# sparkfun-samd21g-r3.net
KiCad netlist of a schematic drawn in EAGLE
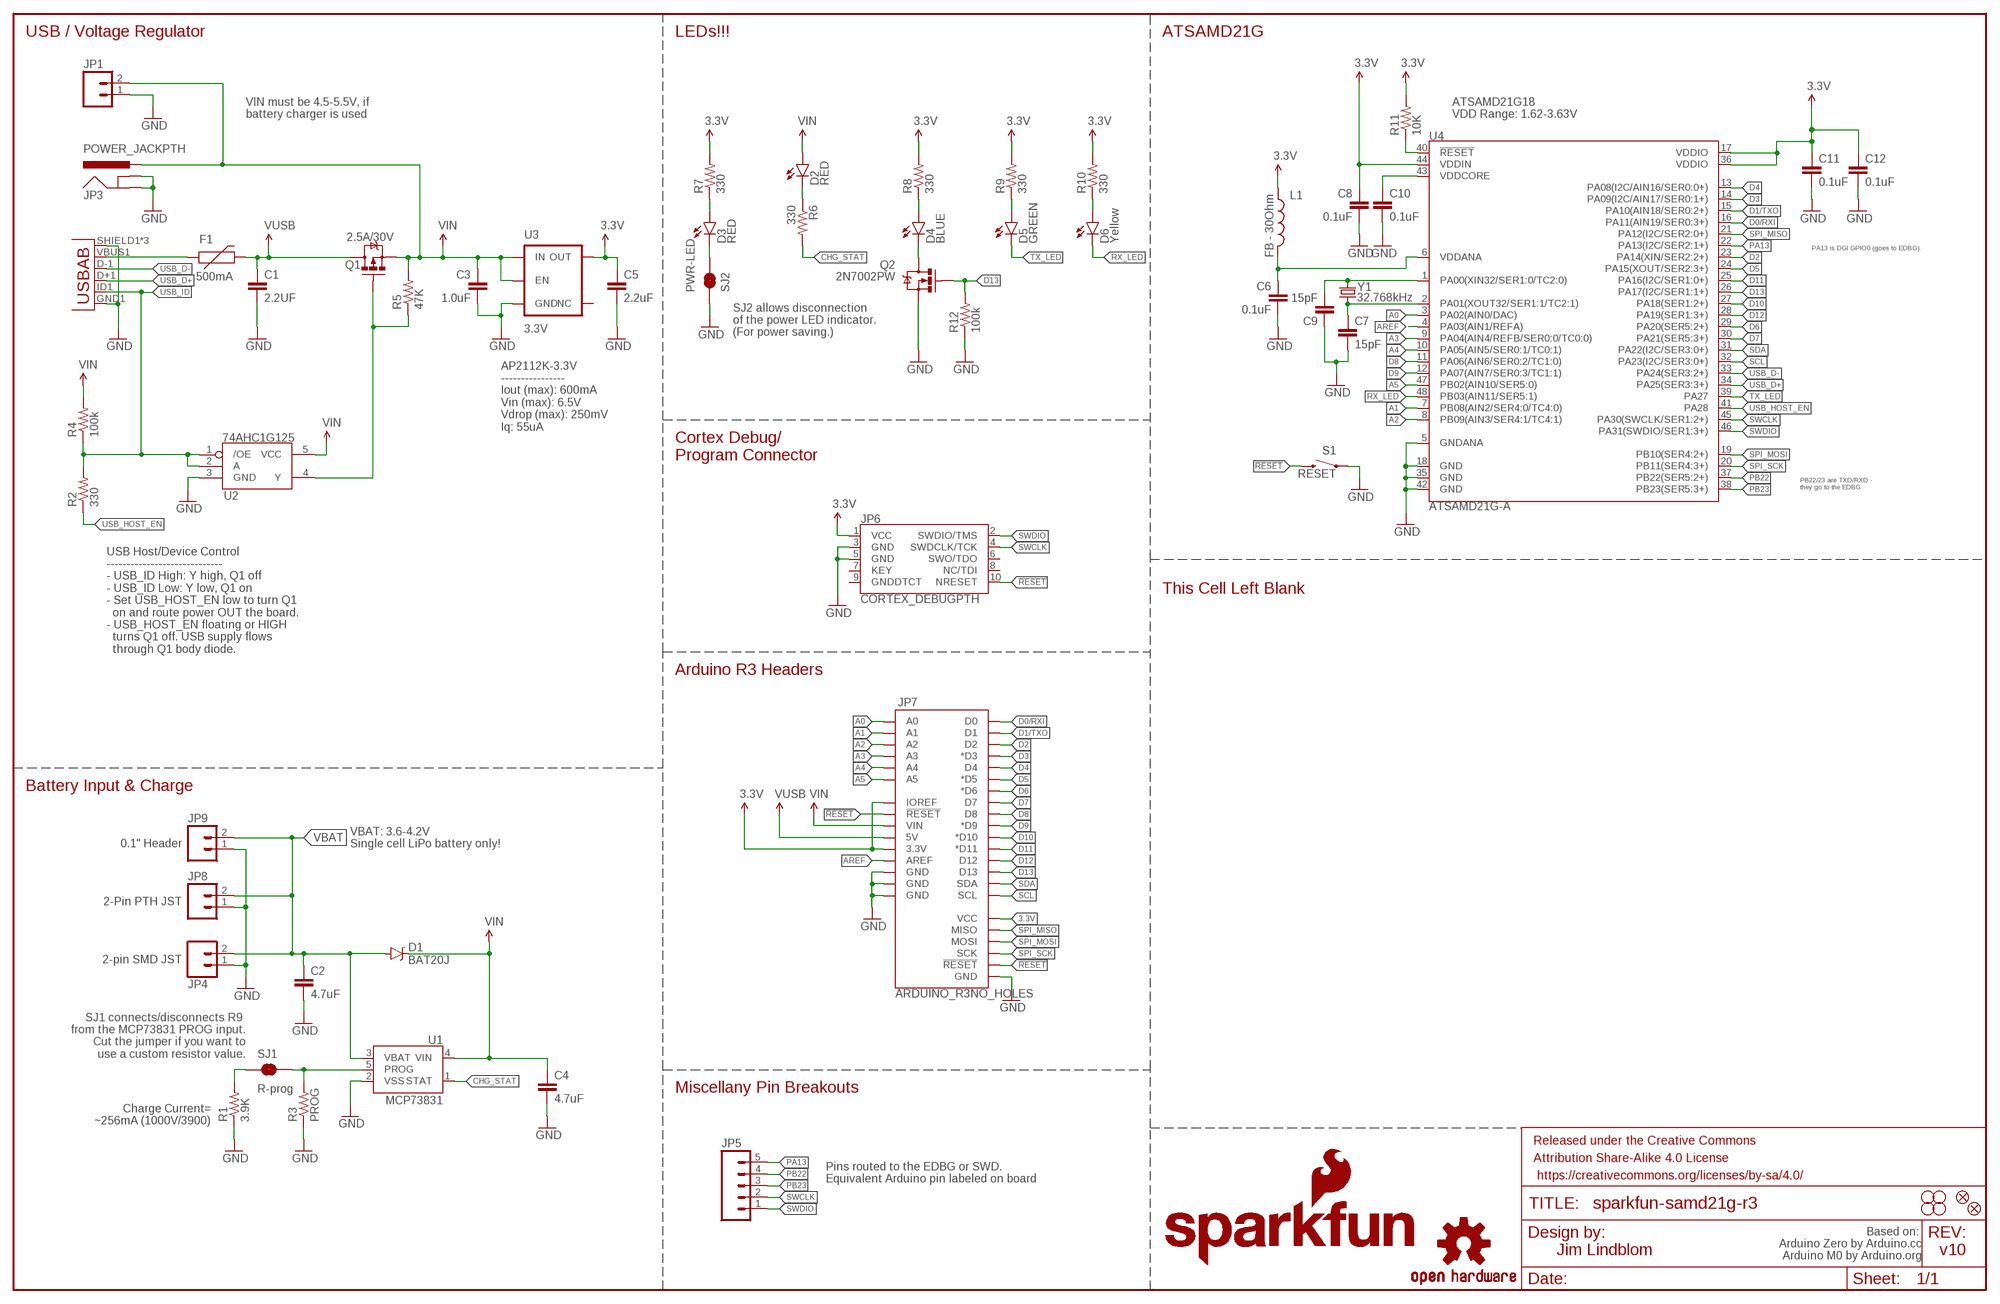
[diagram p0: schematic, sheet 1]

(export (version "E")
  (design (tool "Eeschema 10.0.6"))
  (components
    (comp (ref "C1")
      (value "2.2UF")
      (footprint "eagle-import:1206")
      (libsource (lib "eagle-import") (part "2.2UF50V10%(1206)"))
    )
    (comp (ref "C2")
      (value "4.7uF")
      (footprint "eagle-import:0603-CAP")
      (libsource (lib "eagle-import") (part "4.7UF-6.3V-10%(0603)0603"))
    )
    (comp (ref "C3")
      (value "1.0uF")
      (footprint "eagle-import:0805-CAP")
      (libsource (lib "eagle-import") (part "1.0UF-25V-+80/-20(0805){dblquote}"))
    )
    (comp (ref "C4")
      (value "4.7uF")
      (footprint "eagle-import:0603-CAP")
      (libsource (lib "eagle-import") (part "4.7UF-6.3V-10%(0603)0603"))
    )
    (comp (ref "C5")
      (value "2.2uF")
      (footprint "eagle-import:0603-CAP")
      (libsource (lib "eagle-import") (part "2.2UF-10V-20%(0603)"))
    )
    (comp (ref "C6")
      (value "0.1uF")
      (footprint "eagle-import:0603-CAP")
      (libsource (lib "eagle-import") (part "0.1UF-25V(+80/-20%)(0603)"))
    )
    (comp (ref "C7")
      (value "15pF")
      (footprint "eagle-import:0603-CAP")
      (libsource (lib "eagle-import") (part "15PF-50V-5%(0603)"))
    )
    (comp (ref "C8")
      (value "0.1uF")
      (footprint "eagle-import:0603-CAP")
      (libsource (lib "eagle-import") (part "0.1UF-25V(+80/-20%)(0603)"))
    )
    (comp (ref "C9")
      (value "15pF")
      (footprint "eagle-import:0603-CAP")
      (libsource (lib "eagle-import") (part "15PF-50V-5%(0603)"))
    )
    (comp (ref "C10")
      (value "0.1uF")
      (footprint "eagle-import:0603-CAP")
      (libsource (lib "eagle-import") (part "0.1UF-25V(+80/-20%)(0603)"))
    )
    (comp (ref "C11")
      (value "0.1uF")
      (footprint "eagle-import:0603-CAP")
      (libsource (lib "eagle-import") (part "0.1UF-25V(+80/-20%)(0603)"))
    )
    (comp (ref "C12")
      (value "0.1uF")
      (footprint "eagle-import:0603-CAP")
      (libsource (lib "eagle-import") (part "0.1UF-25V(+80/-20%)(0603)"))
    )
    (comp (ref "D1")
      (value "BAT20J")
      (footprint "eagle-import:SOD-323")
      (libsource (lib "eagle-import") (part "DIODE-SCHOTTKY-BAT20J"))
    )
    (comp (ref "D2")
      (value "RED")
      (footprint "eagle-import:LED-0603")
      (libsource (lib "eagle-import") (part "LED-RED0603"))
    )
    (comp (ref "D3")
      (value "RED")
      (footprint "eagle-import:LED-0603")
      (libsource (lib "eagle-import") (part "LED-RED0603"))
    )
    (comp (ref "D4")
      (value "BLUE")
      (footprint "eagle-import:LED-0603")
      (libsource (lib "eagle-import") (part "LED-BLUE0603"))
    )
    (comp (ref "D5")
      (value "GREEN")
      (footprint "eagle-import:LED-0603")
      (libsource (lib "eagle-import") (part "LED-GREEN0603"))
    )
    (comp (ref "D6")
      (value "Yellow")
      (footprint "eagle-import:LED-0603")
      (libsource (lib "eagle-import") (part "LED-YELLOW0603"))
    )
    (comp (ref "F1")
      (value "500mA")
      (footprint "eagle-import:PTC-1206")
      (libsource (lib "eagle-import") (part "PTCSMD"))
    )
    (comp (ref "FID1")
      (value "FIDUCIAL1X2")
      (footprint "eagle-import:FIDUCIAL-1X2")
      (libsource (lib "eagle-import") (part "FIDUCIAL1X2"))
    )
    (comp (ref "FID2")
      (value "FIDUCIAL1X2")
      (footprint "eagle-import:FIDUCIAL-1X2")
      (libsource (lib "eagle-import") (part "FIDUCIAL1X2"))
    )
    (comp (ref "FRAME1")
      (value "FRAME-LEDGER")
      (footprint "eagle-import:CREATIVE_COMMONS")
      (libsource (lib "eagle-import") (part "FRAME-LEDGER"))
    )
    (comp (ref "JP1")
      (value "M02PTH")
      (footprint "eagle-import:1X02")
      (libsource (lib "eagle-import") (part "M02PTH"))
    )
    (comp (ref "JP2")
      (value "USB-ABCONN-11794")
      (footprint "eagle-import:USB-AB-MICRO-SMD_V03")
      (libsource (lib "eagle-import") (part "USB-ABCONN-11794"))
    )
    (comp (ref "JP3")
      (value "POWER_JACKPTH")
      (footprint "eagle-import:POWER_JACK_PTH")
      (libsource (lib "eagle-import") (part "POWER_JACKPTH"))
    )
    (comp (ref "JP4")
      (value "M02-JST-2MM-SMT")
      (footprint "eagle-import:JST-2-SMD")
      (libsource (lib "eagle-import") (part "M02-JST-2MM-SMT"))
    )
    (comp (ref "JP5")
      (value "M05NO_SILK")
      (footprint "eagle-import:1X05_NO_SILK")
      (libsource (lib "eagle-import") (part "M05NO_SILK"))
    )
    (comp (ref "JP6")
      (value "CORTEX_DEBUGPTH")
      (footprint "eagle-import:2X5-PTH-1.27MM")
      (libsource (lib "eagle-import") (part "CORTEX_DEBUGPTH"))
    )
    (comp (ref "JP7")
      (value "ARDUINO_R3NO_HOLES")
      (footprint "eagle-import:ARDUINO_R3_NO_HOLES")
      (libsource (lib "eagle-import") (part "ARDUINO_R3NO_HOLES"))
    )
    (comp (ref "JP8")
      (value "M02-JST-2-PTH-NO_SILK")
      (footprint "eagle-import:JST-2-PTH-NS")
      (libsource (lib "eagle-import") (part "M02-JST-2-PTH-NO_SILK"))
    )
    (comp (ref "JP9")
      (value "M021X02_NO_SILK")
      (footprint "eagle-import:1X02_NO_SILK")
      (libsource (lib "eagle-import") (part "M021X02_NO_SILK"))
    )
    (comp (ref "L1")
      (value "FB - 30Ohm")
      (footprint "eagle-import:0603")
      (libsource (lib "eagle-import") (part "INDUCTOR0603"))
    )
    (comp (ref "LOGO1")
      (value "SFE_LOGO_NAME_FLAME.2_INCH")
      (footprint "eagle-import:SFE_LOGO_NAME_FLAME_.2")
      (libsource (lib "eagle-import") (part "SFE_LOGO_NAME_FLAME.2_INCH"))
    )
    (comp (ref "LOGO2")
      (value "SFE_LOGO_NAME_FLAME.4_INCH")
      (footprint "eagle-import:SFE_LOGO_NAME_FLAME_.4")
      (libsource (lib "eagle-import") (part "SFE_LOGO_NAME_FLAME.4_INCH"))
    )
    (comp (ref "LOGO3")
      (value "OSHW-LOGOS")
      (footprint "eagle-import:OSHW-LOGO-S")
      (libsource (lib "eagle-import") (part "OSHW-LOGOS"))
    )
    (comp (ref "LOGO4")
      (value "OSHW-LOGOL")
      (footprint "eagle-import:OSHW-LOGO-L")
      (libsource (lib "eagle-import") (part "OSHW-LOGOL"))
    )
    (comp (ref "Q1")
      (value "2.5A/30V")
      (footprint "eagle-import:SOT23-3")
      (libsource (lib "eagle-import") (part "MOSFET-PCHANNELDMG2307L"))
    )
    (comp (ref "Q2")
      (value "2N7002PW")
      (footprint "eagle-import:SOT323")
      (libsource (lib "eagle-import") (part "MOSFET-NCHANNEL2N7002PW"))
    )
    (comp (ref "R1")
      (value "3.9K")
      (footprint "eagle-import:0603")
      (libsource (lib "eagle-import") (part "3.9KOHM1/10W1%(0603)"))
    )
    (comp (ref "R2")
      (value "330")
      (footprint "eagle-import:0603-RES")
      (libsource (lib "eagle-import") (part "330OHM1/10W1%(0603)"))
    )
    (comp (ref "R3")
      (value "PROG")
      (footprint "eagle-import:1_6W-RES")
      (libsource (lib "eagle-import") (part "RESISTORPTH-1/6W"))
    )
    (comp (ref "R4")
      (value "100k")
      (footprint "eagle-import:0603-RES")
      (libsource (lib "eagle-import") (part "100KOHM-1/10W-1%(0603)"))
    )
    (comp (ref "R5")
      (value "47K")
      (footprint "eagle-import:0603-RES")
      (libsource (lib "eagle-import") (part "47KOHM1/10W1%(0603)"))
    )
    (comp (ref "R6")
      (value "330")
      (footprint "eagle-import:0603-RES")
      (libsource (lib "eagle-import") (part "330OHM1/10W1%(0603)"))
    )
    (comp (ref "R7")
      (value "330")
      (footprint "eagle-import:0603-RES")
      (libsource (lib "eagle-import") (part "330OHM1/10W1%(0603)"))
    )
    (comp (ref "R8")
      (value "330")
      (footprint "eagle-import:0603-RES")
      (libsource (lib "eagle-import") (part "330OHM1/10W1%(0603)"))
    )
    (comp (ref "R9")
      (value "330")
      (footprint "eagle-import:0603-RES")
      (libsource (lib "eagle-import") (part "330OHM1/10W1%(0603)"))
    )
    (comp (ref "R10")
      (value "330")
      (footprint "eagle-import:0603-RES")
      (libsource (lib "eagle-import") (part "330OHM1/10W1%(0603)"))
    )
    (comp (ref "R11")
      (value "10K")
      (footprint "eagle-import:0603-RES")
      (libsource (lib "eagle-import") (part "10KOHM-1/10W-1%(0603)0603"))
    )
    (comp (ref "R12")
      (value "100k")
      (footprint "eagle-import:0603-RES")
      (libsource (lib "eagle-import") (part "100KOHM-1/10W-1%(0603)"))
    )
    (comp (ref "S1")
      (value "RESET")
      (footprint "eagle-import:TACTILE-SWITCH-SMD")
      (libsource (lib "eagle-import") (part "SWITCH-MOMENTARY-2SMD"))
    )
    (comp (ref "SJ1")
      (value "R-prog")
      (footprint "eagle-import:PAD-JUMPER-2-NC_BY_TRACE_YES_SILK")
      (libsource (lib "eagle-import") (part "JUMPER-PAD-2-NC_BY_TRACE"))
    )
    (comp (ref "SJ2")
      (value "PWR-LED")
      (footprint "eagle-import:PAD-JUMPER-2-NC_BY_TRACE_NO_SILK")
      (libsource (lib "eagle-import") (part "JUMPER-PAD-2-NC_BY_TRACENO_SILK"))
    )
    (comp (ref "STANDOFF1")
      (value "STAND-OFF")
      (footprint "eagle-import:STAND-OFF")
      (libsource (lib "eagle-import") (part "STAND-OFF"))
    )
    (comp (ref "STANDOFF2")
      (value "STAND-OFF")
      (footprint "eagle-import:STAND-OFF")
      (libsource (lib "eagle-import") (part "STAND-OFF"))
    )
    (comp (ref "STANDOFF3")
      (value "STAND-OFF")
      (footprint "eagle-import:STAND-OFF")
      (libsource (lib "eagle-import") (part "STAND-OFF"))
    )
    (comp (ref "STANDOFF4")
      (value "STAND-OFF")
      (footprint "eagle-import:STAND-OFF")
      (libsource (lib "eagle-import") (part "STAND-OFF"))
    )
    (comp (ref "U1")
      (value "MCP73831")
      (footprint "eagle-import:SOT23-5")
      (libsource (lib "eagle-import") (part "MCP73831"))
    )
    (comp (ref "U2")
      (value "74AHC1G125")
      (footprint "eagle-import:SOT23-5")
      (libsource (lib "eagle-import") (part "74AHC1G125"))
    )
    (comp (ref "U3")
      (value "3.3V")
      (footprint "eagle-import:SOT23-5")
      (libsource (lib "eagle-import") (part "V_REG_AP2112K-3.3V"))
    )
    (comp (ref "U4")
      (value "ATSAMD21G-A")
      (footprint "eagle-import:TQFP-48")
      (libsource (lib "eagle-import") (part "ATSAMD21G-A"))
    )
    (comp (ref "Y1")
      (value "32.768kHz")
      (footprint "eagle-import:CRYSTAL-SMD-3.2X1.5MM")
      (libsource (lib "eagle-import") (part "CRYSTAL3.2X1.5MM"))
    )
  )
  (nets
    (net (code "1") (name "/~{RESET}") (class "Default")
      (node (ref "JP6") (pin "10") (pinfunction "NRESET_10") (pintype "bidirectional"))
      (node (ref "JP7") (pin "RESET@1") (pinfunction "~{RESET}_RESET@1") (pintype "bidirectional"))
      (node (ref "JP7") (pin "RESET@2") (pinfunction "~{RESET}_RESET@2") (pintype "bidirectional"))
      (node (ref "R11") (pin "1") (pinfunction "1_1") (pintype "passive"))
      (node (ref "S1") (pin "3") (pinfunction "2_3") (pintype "passive"))
      (node (ref "U4") (pin "40") (pinfunction "~{RESET}_40") (pintype "bidirectional"))
    )
    (net (code "2") (name "3.3V") (class "Default")
      (node (ref "C11") (pin "1") (pinfunction "1_1") (pintype "passive"))
      (node (ref "C12") (pin "1") (pinfunction "1_1") (pintype "passive"))
      (node (ref "C5") (pin "1") (pinfunction "1_1") (pintype "passive"))
      (node (ref "C8") (pin "1") (pinfunction "1_1") (pintype "passive"))
      (node (ref "JP6") (pin "1") (pinfunction "VCC_1") (pintype "bidirectional"))
      (node (ref "JP7") (pin "3.3V") (pinfunction "3.3V_3.3V") (pintype "bidirectional"))
      (node (ref "JP7") (pin "IOREF") (pinfunction "IOREF_IOREF") (pintype "bidirectional"))
      (node (ref "JP7") (pin "VCC") (pinfunction "VCC_VCC") (pintype "bidirectional"))
      (node (ref "L1") (pin "1") (pinfunction "1_1") (pintype "passive"))
      (node (ref "R10") (pin "2") (pinfunction "2_2") (pintype "passive"))
      (node (ref "R11") (pin "2") (pinfunction "2_2") (pintype "passive"))
      (node (ref "R7") (pin "2") (pinfunction "2_2") (pintype "passive"))
      (node (ref "R8") (pin "2") (pinfunction "2_2") (pintype "passive"))
      (node (ref "R9") (pin "2") (pinfunction "2_2") (pintype "passive"))
      (node (ref "U3") (pin "5") (pinfunction "OUT_5") (pintype "passive"))
      (node (ref "U4") (pin "17") (pinfunction "VDDIO_17") (pintype "bidirectional"))
      (node (ref "U4") (pin "36") (pinfunction "VDDIO_36") (pintype "bidirectional"))
      (node (ref "U4") (pin "44") (pinfunction "VDDIN_44") (pintype "bidirectional"))
    )
    (net (code "3") (name "A0") (class "Default")
      (node (ref "JP7") (pin "A0") (pinfunction "A0_A0") (pintype "bidirectional"))
      (node (ref "U4") (pin "3") (pinfunction "PA02(AIN0/DAC)_3") (pintype "bidirectional"))
    )
    (net (code "4") (name "A1") (class "Default")
      (node (ref "JP7") (pin "A1") (pinfunction "A1_A1") (pintype "bidirectional"))
      (node (ref "U4") (pin "7") (pinfunction "PB08(AIN2/SER4:0/TC4:0)_7") (pintype "bidirectional"))
    )
    (net (code "5") (name "A2") (class "Default")
      (node (ref "JP7") (pin "A2") (pinfunction "A2_A2") (pintype "bidirectional"))
      (node (ref "U4") (pin "8") (pinfunction "PB09(AIN3/SER4:1/TC4:1)_8") (pintype "bidirectional"))
    )
    (net (code "6") (name "A3") (class "Default")
      (node (ref "JP7") (pin "A3") (pinfunction "A3_A3") (pintype "bidirectional"))
      (node (ref "U4") (pin "9") (pinfunction "PA04(AIN4/REFB/SER0:0/TC0:0)_9") (pintype "bidirectional"))
    )
    (net (code "7") (name "A4") (class "Default")
      (node (ref "JP7") (pin "A4") (pinfunction "A4_A4") (pintype "bidirectional"))
      (node (ref "U4") (pin "10") (pinfunction "PA05(AIN5/SER0:1/TC0:1)_10") (pintype "bidirectional"))
    )
    (net (code "8") (name "A5") (class "Default")
      (node (ref "JP7") (pin "A5") (pinfunction "A5_A5") (pintype "bidirectional"))
      (node (ref "U4") (pin "47") (pinfunction "PB02(AIN10/SER5:0)_47") (pintype "bidirectional"))
    )
    (net (code "9") (name "AREF") (class "Default")
      (node (ref "JP7") (pin "AREF") (pinfunction "AREF_AREF") (pintype "bidirectional"))
      (node (ref "U4") (pin "4") (pinfunction "PA03(AIN1/REFA)_4") (pintype "bidirectional"))
    )
    (net (code "10") (name "CHG_STAT") (class "Default")
      (node (ref "R6") (pin "2") (pinfunction "2_2") (pintype "passive"))
      (node (ref "U1") (pin "1") (pinfunction "STAT_1") (pintype "output"))
    )
    (net (code "11") (name "D0{slash}RXI") (class "Default")
      (node (ref "JP7") (pin "D0") (pinfunction "D0_D0") (pintype "bidirectional"))
      (node (ref "U4") (pin "16") (pinfunction "PA11(AIN19/SER0:3+)_16") (pintype "bidirectional"))
    )
    (net (code "12") (name "D1{slash}TXO") (class "Default")
      (node (ref "JP7") (pin "D1") (pinfunction "D1_D1") (pintype "bidirectional"))
      (node (ref "U4") (pin "15") (pinfunction "PA10(AIN18/SER0:2+)_15") (pintype "bidirectional"))
    )
    (net (code "13") (name "D2") (class "Default")
      (node (ref "JP7") (pin "D2") (pinfunction "D2_D2") (pintype "bidirectional"))
      (node (ref "U4") (pin "23") (pinfunction "PA14(XIN/SER2:2+)_23") (pintype "bidirectional"))
    )
    (net (code "14") (name "D3") (class "Default")
      (node (ref "JP7") (pin "D3") (pinfunction "*D3_D3") (pintype "bidirectional"))
      (node (ref "U4") (pin "14") (pinfunction "PA09(I2C/AIN17/SER0:1+)_14") (pintype "bidirectional"))
    )
    (net (code "15") (name "D4") (class "Default")
      (node (ref "JP7") (pin "D4") (pinfunction "D4_D4") (pintype "bidirectional"))
      (node (ref "U4") (pin "13") (pinfunction "PA08(I2C/AIN16/SER0:0+)_13") (pintype "bidirectional"))
    )
    (net (code "16") (name "D5") (class "Default")
      (node (ref "JP7") (pin "D5") (pinfunction "*D5_D5") (pintype "bidirectional"))
      (node (ref "U4") (pin "24") (pinfunction "PA15(XOUT/SER2:3+)_24") (pintype "bidirectional"))
    )
    (net (code "17") (name "D6") (class "Default")
      (node (ref "JP7") (pin "D6") (pinfunction "*D6_D6") (pintype "bidirectional"))
      (node (ref "U4") (pin "29") (pinfunction "PA20(SER5:2+)_29") (pintype "bidirectional"))
    )
    (net (code "18") (name "D7") (class "Default")
      (node (ref "JP7") (pin "D7") (pinfunction "D7_D7") (pintype "bidirectional"))
      (node (ref "U4") (pin "30") (pinfunction "PA21(SER5:3+)_30") (pintype "bidirectional"))
    )
    (net (code "19") (name "D8") (class "Default")
      (node (ref "JP7") (pin "D8") (pinfunction "D8_D8") (pintype "bidirectional"))
      (node (ref "U4") (pin "11") (pinfunction "PA06(AIN6/SER0:2/TC1:0)_11") (pintype "bidirectional"))
    )
    (net (code "20") (name "D9") (class "Default")
      (node (ref "JP7") (pin "D9") (pinfunction "*D9_D9") (pintype "bidirectional"))
      (node (ref "U4") (pin "12") (pinfunction "PA07(AIN7/SER0:3/TC1:1)_12") (pintype "bidirectional"))
    )
    (net (code "21") (name "D10") (class "Default")
      (node (ref "JP7") (pin "D10") (pinfunction "*D10_D10") (pintype "bidirectional"))
      (node (ref "U4") (pin "27") (pinfunction "PA18(SER1:2+)_27") (pintype "bidirectional"))
    )
    (net (code "22") (name "D11") (class "Default")
      (node (ref "JP7") (pin "D11") (pinfunction "*D11_D11") (pintype "bidirectional"))
      (node (ref "U4") (pin "25") (pinfunction "PA16(I2C/SER1:0+)_25") (pintype "bidirectional"))
    )
    (net (code "23") (name "D12") (class "Default")
      (node (ref "JP7") (pin "D12") (pinfunction "D12_D12") (pintype "bidirectional"))
      (node (ref "U4") (pin "28") (pinfunction "PA19(SER1:3+)_28") (pintype "bidirectional"))
    )
    (net (code "24") (name "D13") (class "Default")
      (node (ref "JP7") (pin "D13") (pinfunction "D13_D13") (pintype "bidirectional"))
      (node (ref "Q2") (pin "1") (pinfunction "G_1") (pintype "passive"))
      (node (ref "R12") (pin "2") (pinfunction "2_2") (pintype "passive"))
      (node (ref "U4") (pin "26") (pinfunction "PA17(I2C/SER1:1+)_26") (pintype "bidirectional"))
    )
    (net (code "25") (name "GND") (class "Default")
      (node (ref "C1") (pin "2") (pinfunction "2_2") (pintype "passive"))
      (node (ref "C10") (pin "2") (pinfunction "2_2") (pintype "passive"))
      (node (ref "C11") (pin "2") (pinfunction "2_2") (pintype "passive"))
      (node (ref "C12") (pin "2") (pinfunction "2_2") (pintype "passive"))
      (node (ref "C2") (pin "2") (pinfunction "2_2") (pintype "passive"))
      (node (ref "C3") (pin "2") (pinfunction "2_2") (pintype "passive"))
      (node (ref "C4") (pin "2") (pinfunction "2_2") (pintype "passive"))
      (node (ref "C5") (pin "2") (pinfunction "2_2") (pintype "passive"))
      (node (ref "C6") (pin "2") (pinfunction "2_2") (pintype "passive"))
      (node (ref "C7") (pin "2") (pinfunction "2_2") (pintype "passive"))
      (node (ref "C8") (pin "2") (pinfunction "2_2") (pintype "passive"))
      (node (ref "C9") (pin "1") (pinfunction "1_1") (pintype "passive"))
      (node (ref "JP1") (pin "1") (pinfunction "1_1") (pintype "passive"))
      (node (ref "JP2") (pin "GND1") (pinfunction "GND_GND1") (pintype "bidirectional"))
      (node (ref "JP2") (pin "SHIELD1") (pinfunction "SHIELD_SHIELD1") (pintype "bidirectional"))
      (node (ref "JP2") (pin "SHIELD2") (pinfunction "SHIELD_SHIELD2") (pintype "bidirectional"))
      (node (ref "JP2") (pin "SHIELD3") (pinfunction "SHIELD_SHIELD3") (pintype "bidirectional"))
      (node (ref "JP3") (pin "GND") (pinfunction "GND_GND") (pintype "bidirectional"))
      (node (ref "JP3") (pin "GNDBREAK") (pinfunction "GNDBREAK_GNDBREAK") (pintype "bidirectional"))
      (node (ref "JP4") (pin "1") (pinfunction "2_1") (pintype "passive"))
      (node (ref "JP6") (pin "3") (pinfunction "GND_3") (pintype "bidirectional"))
      (node (ref "JP6") (pin "5") (pinfunction "GND_5") (pintype "bidirectional"))
      (node (ref "JP7") (pin "GND@1") (pinfunction "GND_GND@1") (pintype "bidirectional"))
      (node (ref "JP7") (pin "GND@2") (pinfunction "GND_GND@2") (pintype "bidirectional"))
      (node (ref "JP7") (pin "GND@3") (pinfunction "GND_GND@3") (pintype "bidirectional"))
      (node (ref "JP7") (pin "GND@4") (pinfunction "GND_GND@4") (pintype "bidirectional"))
      (node (ref "JP8") (pin "1") (pinfunction "1_1") (pintype "passive"))
      (node (ref "JP9") (pin "1") (pinfunction "1_1") (pintype "passive"))
      (node (ref "Q2") (pin "2") (pinfunction "S_2") (pintype "passive"))
      (node (ref "R1") (pin "1") (pinfunction "1_1") (pintype "passive"))
      (node (ref "R12") (pin "1") (pinfunction "1_1") (pintype "passive"))
      (node (ref "R3") (pin "1") (pinfunction "1_1") (pintype "passive"))
      (node (ref "S1") (pin "1") (pinfunction "1_1") (pintype "passive"))
      (node (ref "SJ2") (pin "1") (pinfunction "1_1") (pintype "passive"))
      (node (ref "U1") (pin "2") (pinfunction "VSS_2") (pintype "power_in"))
      (node (ref "U2") (pin "3") (pinfunction "GND_3") (pintype "bidirectional"))
      (node (ref "U3") (pin "2") (pinfunction "GND_2") (pintype "input"))
      (node (ref "U4") (pin "18") (pinfunction "GND_18") (pintype "bidirectional"))
      (node (ref "U4") (pin "35") (pinfunction "GND_35") (pintype "bidirectional"))
      (node (ref "U4") (pin "42") (pinfunction "GND_42") (pintype "bidirectional"))
      (node (ref "U4") (pin "5") (pinfunction "GNDANA_5") (pintype "bidirectional"))
    )
    (net (code "26") (name "Net-(D2-PadC)") (class "Default")
      (node (ref "D2") (pin "C") (pinfunction "C_C") (pintype "passive"))
      (node (ref "R6") (pin "1") (pinfunction "1_1") (pintype "passive"))
    )
    (net (code "27") (name "Net-(D3-PadA)") (class "Default")
      (node (ref "D3") (pin "A") (pinfunction "A_A") (pintype "passive"))
      (node (ref "R7") (pin "1") (pinfunction "1_1") (pintype "passive"))
    )
    (net (code "28") (name "Net-(D3-PadC)") (class "Default")
      (node (ref "D3") (pin "C") (pinfunction "C_C") (pintype "passive"))
      (node (ref "SJ2") (pin "2") (pinfunction "2_2") (pintype "passive"))
    )
    (net (code "29") (name "Net-(D4-PadA)") (class "Default")
      (node (ref "D4") (pin "A") (pinfunction "A_A") (pintype "passive"))
      (node (ref "R8") (pin "1") (pinfunction "1_1") (pintype "passive"))
    )
    (net (code "30") (name "Net-(D5-PadA)") (class "Default")
      (node (ref "D5") (pin "A") (pinfunction "A_A") (pintype "passive"))
      (node (ref "R9") (pin "1") (pinfunction "1_1") (pintype "passive"))
    )
    (net (code "31") (name "Net-(D6-PadA)") (class "Default")
      (node (ref "D6") (pin "A") (pinfunction "A_A") (pintype "passive"))
      (node (ref "R10") (pin "1") (pinfunction "1_1") (pintype "passive"))
    )
    (net (code "32") (name "Net-(JP2-VBUS)") (class "Default")
      (node (ref "F1") (pin "1") (pinfunction "1_1") (pintype "bidirectional"))
      (node (ref "JP2") (pin "VBUS1") (pinfunction "VBUS_VBUS1") (pintype "bidirectional"))
    )
    (net (code "33") (name "Net-(Q1-G)") (class "Default")
      (node (ref "Q1") (pin "1") (pinfunction "G_1") (pintype "passive"))
      (node (ref "R5") (pin "1") (pinfunction "1_1") (pintype "passive"))
      (node (ref "U2") (pin "4") (pinfunction "Y_4") (pintype "bidirectional"))
    )
    (net (code "34") (name "Net-(Q2-D)") (class "Default")
      (node (ref "D4") (pin "C") (pinfunction "C_C") (pintype "passive"))
      (node (ref "Q2") (pin "3") (pinfunction "D_3") (pintype "passive"))
    )
    (net (code "35") (name "Net-(R1-Pad2)") (class "Default")
      (node (ref "R1") (pin "2") (pinfunction "2_2") (pintype "passive"))
      (node (ref "SJ1") (pin "1") (pinfunction "1_1") (pintype "passive"))
    )
    (net (code "36") (name "Net-(U1-PROG)") (class "Default")
      (node (ref "R3") (pin "2") (pinfunction "2_2") (pintype "passive"))
      (node (ref "SJ1") (pin "2") (pinfunction "2_2") (pintype "passive"))
      (node (ref "U1") (pin "5") (pinfunction "PROG_5") (pintype "input"))
    )
    (net (code "37") (name "Net-(U4-PA00(XIN32{slash}SER1:0{slash}TC2:0))") (class "Default")
      (node (ref "C9") (pin "2") (pinfunction "2_2") (pintype "passive"))
      (node (ref "U4") (pin "1") (pinfunction "PA00(XIN32/SER1:0/TC2:0)_1") (pintype "bidirectional"))
      (node (ref "Y1") (pin "P$2") (pinfunction "2_P$2") (pintype "passive"))
    )
    (net (code "38") (name "Net-(U4-PA01(XOUT32{slash}SER1:1{slash}TC2:1))") (class "Default")
      (node (ref "C7") (pin "1") (pinfunction "1_1") (pintype "passive"))
      (node (ref "U4") (pin "2") (pinfunction "PA01(XOUT32/SER1:1/TC2:1)_2") (pintype "bidirectional"))
      (node (ref "Y1") (pin "P$1") (pinfunction "1_P$1") (pintype "passive"))
    )
    (net (code "39") (name "Net-(U4-VDDANA)") (class "Default")
      (node (ref "C6") (pin "1") (pinfunction "1_1") (pintype "passive"))
      (node (ref "L1") (pin "2") (pinfunction "2_2") (pintype "passive"))
      (node (ref "U4") (pin "6") (pinfunction "VDDANA_6") (pintype "bidirectional"))
    )
    (net (code "40") (name "Net-(U4-VDDCORE)") (class "Default")
      (node (ref "C10") (pin "1") (pinfunction "1_1") (pintype "passive"))
      (node (ref "U4") (pin "43") (pinfunction "VDDCORE_43") (pintype "bidirectional"))
    )
    (net (code "41") (name "PA13") (class "Default")
      (node (ref "JP5") (pin "5") (pinfunction "5_5") (pintype "passive"))
      (node (ref "U4") (pin "22") (pinfunction "PA13(I2C/SER2:1+)_22") (pintype "bidirectional"))
    )
    (net (code "42") (name "PB22") (class "Default")
      (node (ref "JP5") (pin "4") (pinfunction "4_4") (pintype "passive"))
      (node (ref "U4") (pin "37") (pinfunction "PB22(SER5:2+)_37") (pintype "bidirectional"))
    )
    (net (code "43") (name "PB23") (class "Default")
      (node (ref "JP5") (pin "3") (pinfunction "3_3") (pintype "passive"))
      (node (ref "U4") (pin "38") (pinfunction "PB23(SER5:3+)_38") (pintype "bidirectional"))
    )
    (net (code "44") (name "RX_LED") (class "Default")
      (node (ref "D6") (pin "C") (pinfunction "C_C") (pintype "passive"))
      (node (ref "U4") (pin "48") (pinfunction "PB03(AIN11/SER5:1)_48") (pintype "bidirectional"))
    )
    (net (code "45") (name "SCL") (class "Default")
      (node (ref "JP7") (pin "SCL") (pinfunction "SCL_SCL") (pintype "bidirectional"))
      (node (ref "U4") (pin "32") (pinfunction "PA23(I2C/SER3:0+)_32") (pintype "bidirectional"))
    )
    (net (code "46") (name "SDA") (class "Default")
      (node (ref "JP7") (pin "SDA") (pinfunction "SDA_SDA") (pintype "bidirectional"))
      (node (ref "U4") (pin "31") (pinfunction "PA22(I2C/SER3:0+)_31") (pintype "bidirectional"))
    )
    (net (code "47") (name "SPI_MISO") (class "Default")
      (node (ref "JP7") (pin "MISO") (pinfunction "MISO_MISO") (pintype "bidirectional"))
      (node (ref "U4") (pin "21") (pinfunction "PA12(I2C/SER2:0+)_21") (pintype "bidirectional"))
    )
    (net (code "48") (name "SPI_MOSI") (class "Default")
      (node (ref "JP7") (pin "MOSI") (pinfunction "MOSI_MOSI") (pintype "bidirectional"))
      (node (ref "U4") (pin "19") (pinfunction "PB10(SER4:2+)_19") (pintype "bidirectional"))
    )
    (net (code "49") (name "SPI_SCK") (class "Default")
      (node (ref "JP7") (pin "SCK") (pinfunction "SCK_SCK") (pintype "bidirectional"))
      (node (ref "U4") (pin "20") (pinfunction "PB11(SER4:3+)_20") (pintype "bidirectional"))
    )
    (net (code "50") (name "SWCLK") (class "Default")
      (node (ref "JP5") (pin "2") (pinfunction "2_2") (pintype "passive"))
      (node (ref "JP6") (pin "4") (pinfunction "SWDCLK/TCK_4") (pintype "bidirectional"))
      (node (ref "U4") (pin "45") (pinfunction "PA30(SWCLK/SER1:2+)_45") (pintype "bidirectional"))
    )
    (net (code "51") (name "SWDIO") (class "Default")
      (node (ref "JP5") (pin "1") (pinfunction "1_1") (pintype "passive"))
      (node (ref "JP6") (pin "2") (pinfunction "SWDIO/TMS_2") (pintype "bidirectional"))
      (node (ref "U4") (pin "46") (pinfunction "PA31(SWDIO/SER1:3+)_46") (pintype "bidirectional"))
    )
    (net (code "52") (name "TX_LED") (class "Default")
      (node (ref "D5") (pin "C") (pinfunction "C_C") (pintype "passive"))
      (node (ref "U4") (pin "39") (pinfunction "PA27_39") (pintype "bidirectional"))
    )
    (net (code "53") (name "USB_D+") (class "Default")
      (node (ref "JP2") (pin "D+1") (pinfunction "D+_D+1") (pintype "bidirectional"))
      (node (ref "U4") (pin "34") (pinfunction "PA25(SER3:3+)_34") (pintype "bidirectional"))
    )
    (net (code "54") (name "USB_D-") (class "Default")
      (node (ref "JP2") (pin "D-1") (pinfunction "D-_D-1") (pintype "bidirectional"))
      (node (ref "U4") (pin "33") (pinfunction "PA24(SER3:2+)_33") (pintype "bidirectional"))
    )
    (net (code "55") (name "USB_HOST_EN") (class "Default")
      (node (ref "R2") (pin "1") (pinfunction "1_1") (pintype "passive"))
      (node (ref "U4") (pin "41") (pinfunction "PA28_41") (pintype "bidirectional"))
    )
    (net (code "56") (name "USB_ID") (class "Default")
      (node (ref "JP2") (pin "ID1") (pinfunction "USBID_ID1") (pintype "bidirectional"))
      (node (ref "R2") (pin "2") (pinfunction "2_2") (pintype "passive"))
      (node (ref "R4") (pin "1") (pinfunction "1_1") (pintype "passive"))
      (node (ref "U2") (pin "1") (pinfunction "/OE_1") (pintype "bidirectional"))
      (node (ref "U2") (pin "2") (pinfunction "A_2") (pintype "bidirectional"))
    )
    (net (code "57") (name "VBAT") (class "Default")
      (node (ref "C2") (pin "1") (pinfunction "1_1") (pintype "passive"))
      (node (ref "D1") (pin "A") (pinfunction "A_A") (pintype "passive"))
      (node (ref "JP4") (pin "2") (pinfunction "1_2") (pintype "passive"))
      (node (ref "JP8") (pin "2") (pinfunction "2_2") (pintype "passive"))
      (node (ref "JP9") (pin "2") (pinfunction "2_2") (pintype "passive"))
      (node (ref "U1") (pin "3") (pinfunction "VBAT_3") (pintype "power_in"))
    )
    (net (code "58") (name "VIN") (class "Default")
      (node (ref "C3") (pin "1") (pinfunction "1_1") (pintype "passive"))
      (node (ref "C4") (pin "1") (pinfunction "1_1") (pintype "passive"))
      (node (ref "D1") (pin "C") (pinfunction "C_C") (pintype "passive"))
      (node (ref "D2") (pin "A") (pinfunction "A_A") (pintype "passive"))
      (node (ref "JP1") (pin "2") (pinfunction "2_2") (pintype "passive"))
      (node (ref "JP3") (pin "PWR") (pinfunction "PWR_PWR") (pintype "bidirectional"))
      (node (ref "JP7") (pin "VIN") (pinfunction "VIN_VIN") (pintype "bidirectional"))
      (node (ref "Q1") (pin "2") (pinfunction "S_2") (pintype "passive"))
      (node (ref "R4") (pin "2") (pinfunction "2_2") (pintype "passive"))
      (node (ref "R5") (pin "2") (pinfunction "2_2") (pintype "passive"))
      (node (ref "U1") (pin "4") (pinfunction "VIN_4") (pintype "power_in"))
      (node (ref "U2") (pin "5") (pinfunction "VCC_5") (pintype "bidirectional"))
      (node (ref "U3") (pin "1") (pinfunction "IN_1") (pintype "input"))
      (node (ref "U3") (pin "3") (pinfunction "EN_3") (pintype "input"))
    )
    (net (code "59") (name "VUSB") (class "Default")
      (node (ref "C1") (pin "1") (pinfunction "1_1") (pintype "passive"))
      (node (ref "F1") (pin "2") (pinfunction "2_2") (pintype "bidirectional"))
      (node (ref "JP7") (pin "5V") (pinfunction "5V_5V") (pintype "bidirectional"))
      (node (ref "Q1") (pin "3") (pinfunction "D_3") (pintype "passive"))
    )
    (net (code "60") (name "unconnected-(JP6-GNDDTCT-Pad9)") (class "Default")
      (node (ref "JP6") (pin "9") (pinfunction "GNDDTCT_9") (pintype "bidirectional"))
    )
    (net (code "61") (name "unconnected-(JP6-KEY-Pad7)") (class "Default")
      (node (ref "JP6") (pin "7") (pinfunction "KEY_7") (pintype "bidirectional"))
    )
    (net (code "62") (name "unconnected-(JP6-NC{slash}TDI-Pad8)") (class "Default")
      (node (ref "JP6") (pin "8") (pinfunction "NC/TDI_8") (pintype "bidirectional"))
    )
    (net (code "63") (name "unconnected-(JP6-SWO{slash}TDO-Pad6)") (class "Default")
      (node (ref "JP6") (pin "6") (pinfunction "SWO/TDO_6") (pintype "bidirectional"))
    )
    (net (code "64") (name "unconnected-(U3-NC-Pad4)") (class "Default")
      (node (ref "U3") (pin "4") (pinfunction "NC_4") (pintype "input"))
    )
  )
)
